# m232.net
KiCad netlist of a schematic drawn in EAGLE
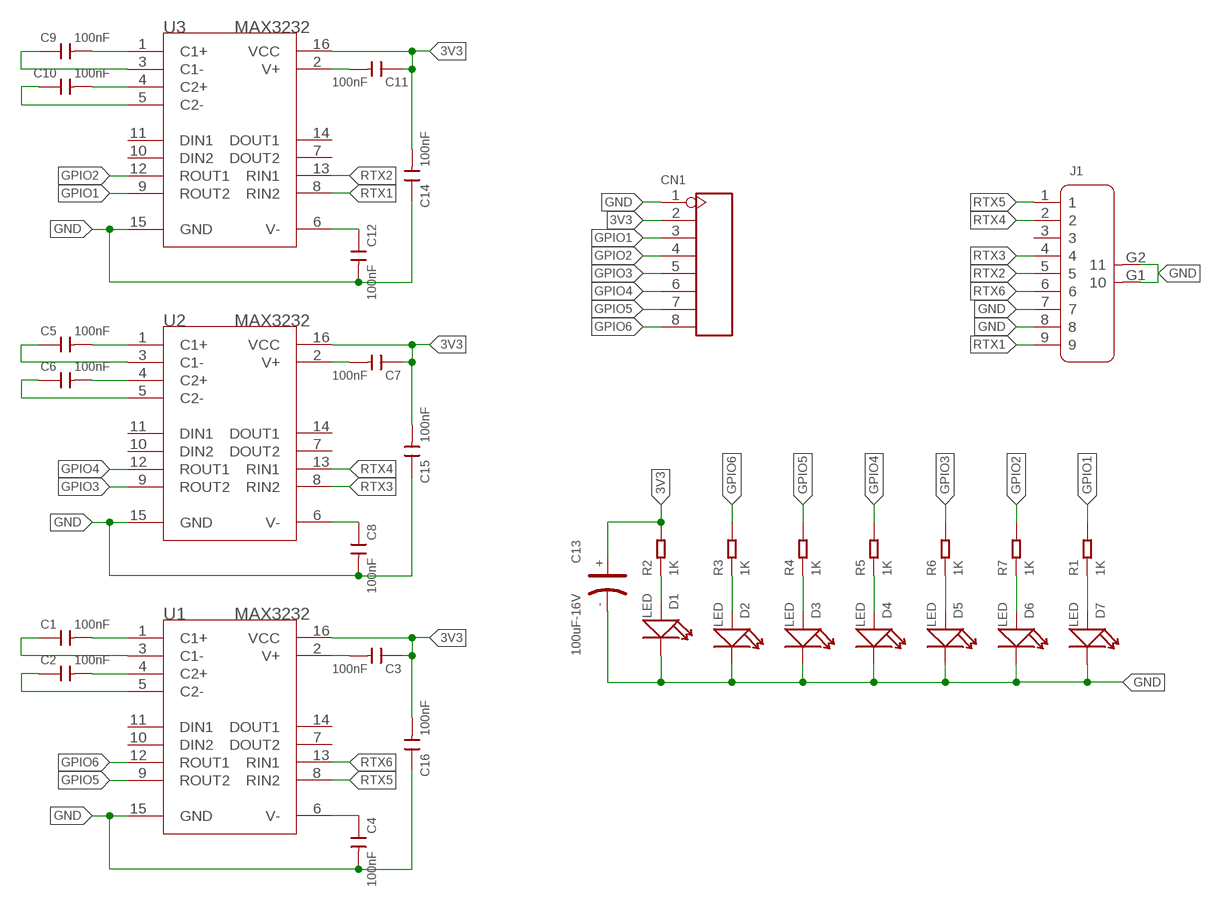
[diagram p0: schematic, sheet 1]

(export (version "E")
  (design (tool "Eeschema 10.0.6"))
  (components
    (comp (ref "C1")
      (value "100nF")
      (footprint "eagle-import:C0805")
      (fields (field (name "MPN") "CC0805KRX7R9BB104"))
      (libsource (lib "eagle-import") (part "CERAMIC-100NF-50V-10%-X7R(0805)"))
    )
    (comp (ref "C2")
      (value "100nF")
      (footprint "eagle-import:C0805")
      (fields (field (name "MPN") "CC0805KRX7R9BB104"))
      (libsource (lib "eagle-import") (part "CERAMIC-100NF-50V-10%-X7R(0805)"))
    )
    (comp (ref "C3")
      (value "100nF")
      (footprint "eagle-import:C0805")
      (fields (field (name "MPN") "CC0805KRX7R9BB104"))
      (libsource (lib "eagle-import") (part "CERAMIC-100NF-50V-10%-X7R(0805)"))
    )
    (comp (ref "C4")
      (value "100nF")
      (footprint "eagle-import:C0805")
      (fields (field (name "MPN") "CC0805KRX7R9BB104"))
      (libsource (lib "eagle-import") (part "CERAMIC-100NF-50V-10%-X7R(0805)"))
    )
    (comp (ref "C5")
      (value "100nF")
      (footprint "eagle-import:C0805")
      (fields (field (name "MPN") "CC0805KRX7R9BB104"))
      (libsource (lib "eagle-import") (part "CERAMIC-100NF-50V-10%-X7R(0805)"))
    )
    (comp (ref "C6")
      (value "100nF")
      (footprint "eagle-import:C0805")
      (fields (field (name "MPN") "CC0805KRX7R9BB104"))
      (libsource (lib "eagle-import") (part "CERAMIC-100NF-50V-10%-X7R(0805)"))
    )
    (comp (ref "C7")
      (value "100nF")
      (footprint "eagle-import:C0805")
      (fields (field (name "MPN") "CC0805KRX7R9BB104"))
      (libsource (lib "eagle-import") (part "CERAMIC-100NF-50V-10%-X7R(0805)"))
    )
    (comp (ref "C8")
      (value "100nF")
      (footprint "eagle-import:C0805")
      (fields (field (name "MPN") "CC0805KRX7R9BB104"))
      (libsource (lib "eagle-import") (part "CERAMIC-100NF-50V-10%-X7R(0805)"))
    )
    (comp (ref "C9")
      (value "100nF")
      (footprint "eagle-import:C0805")
      (fields (field (name "MPN") "CC0805KRX7R9BB104"))
      (libsource (lib "eagle-import") (part "CERAMIC-100NF-50V-10%-X7R(0805)"))
    )
    (comp (ref "C10")
      (value "100nF")
      (footprint "eagle-import:C0805")
      (fields (field (name "MPN") "CC0805KRX7R9BB104"))
      (libsource (lib "eagle-import") (part "CERAMIC-100NF-50V-10%-X7R(0805)"))
    )
    (comp (ref "C11")
      (value "100nF")
      (footprint "eagle-import:C0805")
      (fields (field (name "MPN") "CC0805KRX7R9BB104"))
      (libsource (lib "eagle-import") (part "CERAMIC-100NF-50V-10%-X7R(0805)"))
    )
    (comp (ref "C12")
      (value "100nF")
      (footprint "eagle-import:C0805")
      (fields (field (name "MPN") "CC0805KRX7R9BB104"))
      (libsource (lib "eagle-import") (part "CERAMIC-100NF-50V-10%-X7R(0805)"))
    )
    (comp (ref "C13")
      (value "100uF-16V")
      (footprint "eagle-import:PC-D5.3MM")
      (libsource (lib "eagle-import") (part "DIP-ALUMINUM-100UF-16V(D5-H7MM)"))
    )
    (comp (ref "C14")
      (value "100nF")
      (footprint "eagle-import:C0805")
      (fields (field (name "MPN") "CC0805KRX7R9BB104"))
      (libsource (lib "eagle-import") (part "CERAMIC-100NF-50V-10%-X7R(0805)"))
    )
    (comp (ref "C15")
      (value "100nF")
      (footprint "eagle-import:C0805")
      (fields (field (name "MPN") "CC0805KRX7R9BB104"))
      (libsource (lib "eagle-import") (part "CERAMIC-100NF-50V-10%-X7R(0805)"))
    )
    (comp (ref "C16")
      (value "100nF")
      (footprint "eagle-import:C0805")
      (fields (field (name "MPN") "CC0805KRX7R9BB104"))
      (libsource (lib "eagle-import") (part "CERAMIC-100NF-50V-10%-X7R(0805)"))
    )
    (comp (ref "CN1")
      (value "DIP-BLACK-FEMALE-HEADER-VERT(8P)")
      (footprint "eagle-import:H8-2.54")
      (fields (field (name "MPN") "F185-1108A1BSYC1"))
      (libsource (lib "eagle-import") (part "DIP-BLACK-FEMALE-HEADER-VERT(8P)"))
    )
    (comp (ref "D1")
      (value "LED")
      (footprint "eagle-import:LED-0805")
      (fields (field (name "MPN") "17-215SYGC/S530-E2/TR8"))
      (libsource (lib "eagle-import") (part "SMD-LED-CLEAR-GREEN(0805)"))
    )
    (comp (ref "D2")
      (value "LED")
      (footprint "eagle-import:LED-0805")
      (fields (field (name "MPN") "17-215SYGC/S530-E2/TR8"))
      (libsource (lib "eagle-import") (part "SMD-LED-CLEAR-GREEN(0805)"))
    )
    (comp (ref "D3")
      (value "LED")
      (footprint "eagle-import:LED-0805")
      (fields (field (name "MPN") "17-215SYGC/S530-E2/TR8"))
      (libsource (lib "eagle-import") (part "SMD-LED-CLEAR-GREEN(0805)"))
    )
    (comp (ref "D4")
      (value "LED")
      (footprint "eagle-import:LED-0805")
      (fields (field (name "MPN") "17-215SYGC/S530-E2/TR8"))
      (libsource (lib "eagle-import") (part "SMD-LED-CLEAR-GREEN(0805)"))
    )
    (comp (ref "D5")
      (value "LED")
      (footprint "eagle-import:LED-0805")
      (fields (field (name "MPN") "17-215SYGC/S530-E2/TR8"))
      (libsource (lib "eagle-import") (part "SMD-LED-CLEAR-GREEN(0805)"))
    )
    (comp (ref "D6")
      (value "LED")
      (footprint "eagle-import:LED-0805")
      (fields (field (name "MPN") "17-215SYGC/S530-E2/TR8"))
      (libsource (lib "eagle-import") (part "SMD-LED-CLEAR-GREEN(0805)"))
    )
    (comp (ref "D7")
      (value "LED")
      (footprint "eagle-import:LED-0805")
      (fields (field (name "MPN") "17-215SYGC/S530-E2/TR8"))
      (libsource (lib "eagle-import") (part "SMD-LED-CLEAR-GREEN(0805)"))
    )
    (comp (ref "J1")
      (value "DIP-MALE-DB9-CONNECTOR")
      (footprint "eagle-import:DSUB9+2P-2.77-90D-MALE")
      (libsource (lib "eagle-import") (part "DIP-MALE-DB9-CONNECTOR"))
    )
    (comp (ref "R1")
      (value "1K")
      (footprint "eagle-import:R0805")
      (fields (field (name "MPN") "RC0805JR-071KL"))
      (libsource (lib "eagle-import") (part "SMD-RES-1K-5%-1/8W(0805)"))
    )
    (comp (ref "R2")
      (value "1K")
      (footprint "eagle-import:R0805")
      (fields (field (name "MPN") "RC0805JR-071KL"))
      (libsource (lib "eagle-import") (part "SMD-RES-1K-5%-1/8W(0805)"))
    )
    (comp (ref "R3")
      (value "1K")
      (footprint "eagle-import:R0805")
      (fields (field (name "MPN") "RC0805JR-071KL"))
      (libsource (lib "eagle-import") (part "SMD-RES-1K-5%-1/8W(0805)"))
    )
    (comp (ref "R4")
      (value "1K")
      (footprint "eagle-import:R0805")
      (fields (field (name "MPN") "RC0805JR-071KL"))
      (libsource (lib "eagle-import") (part "SMD-RES-1K-5%-1/8W(0805)"))
    )
    (comp (ref "R5")
      (value "1K")
      (footprint "eagle-import:R0805")
      (fields (field (name "MPN") "RC0805JR-071KL"))
      (libsource (lib "eagle-import") (part "SMD-RES-1K-5%-1/8W(0805)"))
    )
    (comp (ref "R6")
      (value "1K")
      (footprint "eagle-import:R0805")
      (fields (field (name "MPN") "RC0805JR-071KL"))
      (libsource (lib "eagle-import") (part "SMD-RES-1K-5%-1/8W(0805)"))
    )
    (comp (ref "R7")
      (value "1K")
      (footprint "eagle-import:R0805")
      (fields (field (name "MPN") "RC0805JR-071KL"))
      (libsource (lib "eagle-import") (part "SMD-RES-1K-5%-1/8W(0805)"))
    )
    (comp (ref "U1")
      (value "MAX3232")
      (footprint "eagle-import:SOIC16-1.27-10X3.9MM")
      (libsource (lib "eagle-import") (part "RECEIVER-MAX232D(SOIC16)"))
    )
    (comp (ref "U2")
      (value "MAX3232")
      (footprint "eagle-import:SOIC16-1.27-10X3.9MM")
      (libsource (lib "eagle-import") (part "RECEIVER-MAX232D(SOIC16)"))
    )
    (comp (ref "U3")
      (value "MAX3232")
      (footprint "eagle-import:SOIC16-1.27-10X3.9MM")
      (libsource (lib "eagle-import") (part "RECEIVER-MAX232D(SOIC16)"))
    )
  )
  (nets
    (net (code "1") (name "3V3") (class "Default")
      (node (ref "C11") (pin "1") (pinfunction "1_1") (pintype "passive"))
      (node (ref "C13") (pin "+") (pinfunction "+_+") (pintype "passive"))
      (node (ref "C14") (pin "2") (pinfunction "2_2") (pintype "passive"))
      (node (ref "C15") (pin "2") (pinfunction "2_2") (pintype "passive"))
      (node (ref "C16") (pin "2") (pinfunction "2_2") (pintype "passive"))
      (node (ref "C3") (pin "1") (pinfunction "1_1") (pintype "passive"))
      (node (ref "C7") (pin "1") (pinfunction "1_1") (pintype "passive"))
      (node (ref "CN1") (pin "2") (pinfunction "2_2") (pintype "bidirectional"))
      (node (ref "R2") (pin "2") (pinfunction "2_2") (pintype "passive"))
      (node (ref "U1") (pin "16") (pinfunction "VCC_16") (pintype "bidirectional"))
      (node (ref "U2") (pin "16") (pinfunction "VCC_16") (pintype "bidirectional"))
      (node (ref "U3") (pin "16") (pinfunction "VCC_16") (pintype "bidirectional"))
    )
    (net (code "2") (name "GND") (class "Default")
      (node (ref "C12") (pin "2") (pinfunction "2_2") (pintype "passive"))
      (node (ref "C13") (pin "-") (pinfunction "-_-") (pintype "passive"))
      (node (ref "C14") (pin "1") (pinfunction "1_1") (pintype "passive"))
      (node (ref "C15") (pin "1") (pinfunction "1_1") (pintype "passive"))
      (node (ref "C16") (pin "1") (pinfunction "1_1") (pintype "passive"))
      (node (ref "C4") (pin "2") (pinfunction "2_2") (pintype "passive"))
      (node (ref "C8") (pin "2") (pinfunction "2_2") (pintype "passive"))
      (node (ref "CN1") (pin "1") (pinfunction "1_1") (pintype "bidirectional"))
      (node (ref "D1") (pin "-") (pinfunction "-_-") (pintype "passive"))
      (node (ref "D2") (pin "-") (pinfunction "-_-") (pintype "passive"))
      (node (ref "D3") (pin "-") (pinfunction "-_-") (pintype "passive"))
      (node (ref "D4") (pin "-") (pinfunction "-_-") (pintype "passive"))
      (node (ref "D5") (pin "-") (pinfunction "-_-") (pintype "passive"))
      (node (ref "D6") (pin "-") (pinfunction "-_-") (pintype "passive"))
      (node (ref "D7") (pin "-") (pinfunction "-_-") (pintype "passive"))
      (node (ref "J1") (pin "7") (pinfunction "7_7") (pintype "bidirectional"))
      (node (ref "J1") (pin "8") (pinfunction "8_8") (pintype "bidirectional"))
      (node (ref "J1") (pin "G1") (pinfunction "10_G1") (pintype "bidirectional"))
      (node (ref "J1") (pin "G2") (pinfunction "11_G2") (pintype "bidirectional"))
      (node (ref "U1") (pin "15") (pinfunction "GND_15") (pintype "bidirectional"))
      (node (ref "U2") (pin "15") (pinfunction "GND_15") (pintype "bidirectional"))
      (node (ref "U3") (pin "15") (pinfunction "GND_15") (pintype "bidirectional"))
    )
    (net (code "3") (name "GPIO1") (class "Default")
      (node (ref "CN1") (pin "3") (pinfunction "3_3") (pintype "bidirectional"))
      (node (ref "R1") (pin "2") (pinfunction "2_2") (pintype "passive"))
      (node (ref "U3") (pin "9") (pinfunction "ROUT2_9") (pintype "bidirectional"))
    )
    (net (code "4") (name "GPIO2") (class "Default")
      (node (ref "CN1") (pin "4") (pinfunction "4_4") (pintype "bidirectional"))
      (node (ref "R7") (pin "2") (pinfunction "2_2") (pintype "passive"))
      (node (ref "U3") (pin "12") (pinfunction "ROUT1_12") (pintype "bidirectional"))
    )
    (net (code "5") (name "GPIO3") (class "Default")
      (node (ref "CN1") (pin "5") (pinfunction "5_5") (pintype "bidirectional"))
      (node (ref "R6") (pin "2") (pinfunction "2_2") (pintype "passive"))
      (node (ref "U2") (pin "9") (pinfunction "ROUT2_9") (pintype "bidirectional"))
    )
    (net (code "6") (name "GPIO4") (class "Default")
      (node (ref "CN1") (pin "6") (pinfunction "6_6") (pintype "bidirectional"))
      (node (ref "R5") (pin "2") (pinfunction "2_2") (pintype "passive"))
      (node (ref "U2") (pin "12") (pinfunction "ROUT1_12") (pintype "bidirectional"))
    )
    (net (code "7") (name "GPIO5") (class "Default")
      (node (ref "CN1") (pin "7") (pinfunction "7_7") (pintype "bidirectional"))
      (node (ref "R4") (pin "2") (pinfunction "2_2") (pintype "passive"))
      (node (ref "U1") (pin "9") (pinfunction "ROUT2_9") (pintype "bidirectional"))
    )
    (net (code "8") (name "GPIO6") (class "Default")
      (node (ref "CN1") (pin "8") (pinfunction "8_8") (pintype "bidirectional"))
      (node (ref "R3") (pin "2") (pinfunction "2_2") (pintype "passive"))
      (node (ref "U1") (pin "12") (pinfunction "ROUT1_12") (pintype "bidirectional"))
    )
    (net (code "9") (name "Net-(D1-Pad+)") (class "Default")
      (node (ref "D1") (pin "+") (pinfunction "+_+") (pintype "passive"))
      (node (ref "R2") (pin "1") (pinfunction "1_1") (pintype "passive"))
    )
    (net (code "10") (name "Net-(D2-Pad+)") (class "Default")
      (node (ref "D2") (pin "+") (pinfunction "+_+") (pintype "passive"))
      (node (ref "R3") (pin "1") (pinfunction "1_1") (pintype "passive"))
    )
    (net (code "11") (name "Net-(D3-Pad+)") (class "Default")
      (node (ref "D3") (pin "+") (pinfunction "+_+") (pintype "passive"))
      (node (ref "R4") (pin "1") (pinfunction "1_1") (pintype "passive"))
    )
    (net (code "12") (name "Net-(D4-Pad+)") (class "Default")
      (node (ref "D4") (pin "+") (pinfunction "+_+") (pintype "passive"))
      (node (ref "R5") (pin "1") (pinfunction "1_1") (pintype "passive"))
    )
    (net (code "13") (name "Net-(D5-Pad+)") (class "Default")
      (node (ref "D5") (pin "+") (pinfunction "+_+") (pintype "passive"))
      (node (ref "R6") (pin "1") (pinfunction "1_1") (pintype "passive"))
    )
    (net (code "14") (name "Net-(D6-Pad+)") (class "Default")
      (node (ref "D6") (pin "+") (pinfunction "+_+") (pintype "passive"))
      (node (ref "R7") (pin "1") (pinfunction "1_1") (pintype "passive"))
    )
    (net (code "15") (name "Net-(D7-Pad+)") (class "Default")
      (node (ref "D7") (pin "+") (pinfunction "+_+") (pintype "passive"))
      (node (ref "R1") (pin "1") (pinfunction "1_1") (pintype "passive"))
    )
    (net (code "16") (name "Net-(U1-C1+)") (class "Default")
      (node (ref "C1") (pin "2") (pinfunction "2_2") (pintype "passive"))
      (node (ref "U1") (pin "1") (pinfunction "C1+_1") (pintype "bidirectional"))
    )
    (net (code "17") (name "Net-(U1-C1-)") (class "Default")
      (node (ref "C1") (pin "1") (pinfunction "1_1") (pintype "passive"))
      (node (ref "U1") (pin "3") (pinfunction "C1-_3") (pintype "bidirectional"))
    )
    (net (code "18") (name "Net-(U1-C2+)") (class "Default")
      (node (ref "C2") (pin "2") (pinfunction "2_2") (pintype "passive"))
      (node (ref "U1") (pin "4") (pinfunction "C2+_4") (pintype "bidirectional"))
    )
    (net (code "19") (name "Net-(U1-C2-)") (class "Default")
      (node (ref "C2") (pin "1") (pinfunction "1_1") (pintype "passive"))
      (node (ref "U1") (pin "5") (pinfunction "C2-_5") (pintype "bidirectional"))
    )
    (net (code "20") (name "Net-(U1-V+)") (class "Default")
      (node (ref "C3") (pin "2") (pinfunction "2_2") (pintype "passive"))
      (node (ref "U1") (pin "2") (pinfunction "V+_2") (pintype "bidirectional"))
    )
    (net (code "21") (name "Net-(U1-V-)") (class "Default")
      (node (ref "C4") (pin "1") (pinfunction "1_1") (pintype "passive"))
      (node (ref "U1") (pin "6") (pinfunction "V-_6") (pintype "bidirectional"))
    )
    (net (code "22") (name "Net-(U2-C1+)") (class "Default")
      (node (ref "C5") (pin "2") (pinfunction "2_2") (pintype "passive"))
      (node (ref "U2") (pin "1") (pinfunction "C1+_1") (pintype "bidirectional"))
    )
    (net (code "23") (name "Net-(U2-C1-)") (class "Default")
      (node (ref "C5") (pin "1") (pinfunction "1_1") (pintype "passive"))
      (node (ref "U2") (pin "3") (pinfunction "C1-_3") (pintype "bidirectional"))
    )
    (net (code "24") (name "Net-(U2-C2+)") (class "Default")
      (node (ref "C6") (pin "2") (pinfunction "2_2") (pintype "passive"))
      (node (ref "U2") (pin "4") (pinfunction "C2+_4") (pintype "bidirectional"))
    )
    (net (code "25") (name "Net-(U2-C2-)") (class "Default")
      (node (ref "C6") (pin "1") (pinfunction "1_1") (pintype "passive"))
      (node (ref "U2") (pin "5") (pinfunction "C2-_5") (pintype "bidirectional"))
    )
    (net (code "26") (name "Net-(U2-V+)") (class "Default")
      (node (ref "C7") (pin "2") (pinfunction "2_2") (pintype "passive"))
      (node (ref "U2") (pin "2") (pinfunction "V+_2") (pintype "bidirectional"))
    )
    (net (code "27") (name "Net-(U2-V-)") (class "Default")
      (node (ref "C8") (pin "1") (pinfunction "1_1") (pintype "passive"))
      (node (ref "U2") (pin "6") (pinfunction "V-_6") (pintype "bidirectional"))
    )
    (net (code "28") (name "Net-(U3-C1+)") (class "Default")
      (node (ref "C9") (pin "2") (pinfunction "2_2") (pintype "passive"))
      (node (ref "U3") (pin "1") (pinfunction "C1+_1") (pintype "bidirectional"))
    )
    (net (code "29") (name "Net-(U3-C1-)") (class "Default")
      (node (ref "C9") (pin "1") (pinfunction "1_1") (pintype "passive"))
      (node (ref "U3") (pin "3") (pinfunction "C1-_3") (pintype "bidirectional"))
    )
    (net (code "30") (name "Net-(U3-C2+)") (class "Default")
      (node (ref "C10") (pin "2") (pinfunction "2_2") (pintype "passive"))
      (node (ref "U3") (pin "4") (pinfunction "C2+_4") (pintype "bidirectional"))
    )
    (net (code "31") (name "Net-(U3-C2-)") (class "Default")
      (node (ref "C10") (pin "1") (pinfunction "1_1") (pintype "passive"))
      (node (ref "U3") (pin "5") (pinfunction "C2-_5") (pintype "bidirectional"))
    )
    (net (code "32") (name "Net-(U3-V+)") (class "Default")
      (node (ref "C11") (pin "2") (pinfunction "2_2") (pintype "passive"))
      (node (ref "U3") (pin "2") (pinfunction "V+_2") (pintype "bidirectional"))
    )
    (net (code "33") (name "Net-(U3-V-)") (class "Default")
      (node (ref "C12") (pin "1") (pinfunction "1_1") (pintype "passive"))
      (node (ref "U3") (pin "6") (pinfunction "V-_6") (pintype "bidirectional"))
    )
    (net (code "34") (name "RTX1") (class "Default")
      (node (ref "J1") (pin "9") (pinfunction "9_9") (pintype "bidirectional"))
      (node (ref "U3") (pin "8") (pinfunction "RIN2_8") (pintype "bidirectional"))
    )
    (net (code "35") (name "RTX2") (class "Default")
      (node (ref "J1") (pin "5") (pinfunction "5_5") (pintype "bidirectional"))
      (node (ref "U3") (pin "13") (pinfunction "RIN1_13") (pintype "bidirectional"))
    )
    (net (code "36") (name "RTX3") (class "Default")
      (node (ref "J1") (pin "4") (pinfunction "4_4") (pintype "bidirectional"))
      (node (ref "U2") (pin "8") (pinfunction "RIN2_8") (pintype "bidirectional"))
    )
    (net (code "37") (name "RTX4") (class "Default")
      (node (ref "J1") (pin "2") (pinfunction "2_2") (pintype "bidirectional"))
      (node (ref "U2") (pin "13") (pinfunction "RIN1_13") (pintype "bidirectional"))
    )
    (net (code "38") (name "RTX5") (class "Default")
      (node (ref "J1") (pin "1") (pinfunction "1_1") (pintype "bidirectional"))
      (node (ref "U1") (pin "8") (pinfunction "RIN2_8") (pintype "bidirectional"))
    )
    (net (code "39") (name "RTX6") (class "Default")
      (node (ref "J1") (pin "6") (pinfunction "6_6") (pintype "bidirectional"))
      (node (ref "U1") (pin "13") (pinfunction "RIN1_13") (pintype "bidirectional"))
    )
    (net (code "40") (name "unconnected-(J1-Pad3)") (class "Default")
      (node (ref "J1") (pin "3") (pinfunction "3_3") (pintype "bidirectional"))
    )
    (net (code "41") (name "unconnected-(U1-DIN1-Pad11)") (class "Default")
      (node (ref "U1") (pin "11") (pinfunction "DIN1_11") (pintype "input"))
    )
    (net (code "42") (name "unconnected-(U1-DIN2-Pad10)") (class "Default")
      (node (ref "U1") (pin "10") (pinfunction "DIN2_10") (pintype "bidirectional"))
    )
    (net (code "43") (name "unconnected-(U1-DOUT1-Pad14)") (class "Default")
      (node (ref "U1") (pin "14") (pinfunction "DOUT1_14") (pintype "bidirectional"))
    )
    (net (code "44") (name "unconnected-(U1-DOUT2-Pad7)") (class "Default")
      (node (ref "U1") (pin "7") (pinfunction "DOUT2_7") (pintype "bidirectional"))
    )
    (net (code "45") (name "unconnected-(U2-DIN1-Pad11)") (class "Default")
      (node (ref "U2") (pin "11") (pinfunction "DIN1_11") (pintype "input"))
    )
    (net (code "46") (name "unconnected-(U2-DIN2-Pad10)") (class "Default")
      (node (ref "U2") (pin "10") (pinfunction "DIN2_10") (pintype "bidirectional"))
    )
    (net (code "47") (name "unconnected-(U2-DOUT1-Pad14)") (class "Default")
      (node (ref "U2") (pin "14") (pinfunction "DOUT1_14") (pintype "bidirectional"))
    )
    (net (code "48") (name "unconnected-(U2-DOUT2-Pad7)") (class "Default")
      (node (ref "U2") (pin "7") (pinfunction "DOUT2_7") (pintype "bidirectional"))
    )
    (net (code "49") (name "unconnected-(U3-DIN1-Pad11)") (class "Default")
      (node (ref "U3") (pin "11") (pinfunction "DIN1_11") (pintype "input"))
    )
    (net (code "50") (name "unconnected-(U3-DIN2-Pad10)") (class "Default")
      (node (ref "U3") (pin "10") (pinfunction "DIN2_10") (pintype "bidirectional"))
    )
    (net (code "51") (name "unconnected-(U3-DOUT1-Pad14)") (class "Default")
      (node (ref "U3") (pin "14") (pinfunction "DOUT1_14") (pintype "bidirectional"))
    )
    (net (code "52") (name "unconnected-(U3-DOUT2-Pad7)") (class "Default")
      (node (ref "U3") (pin "7") (pinfunction "DOUT2_7") (pintype "bidirectional"))
    )
  )
)
